# Sheet1.net
KiCad netlist of a schematic drawn in Altium Designer
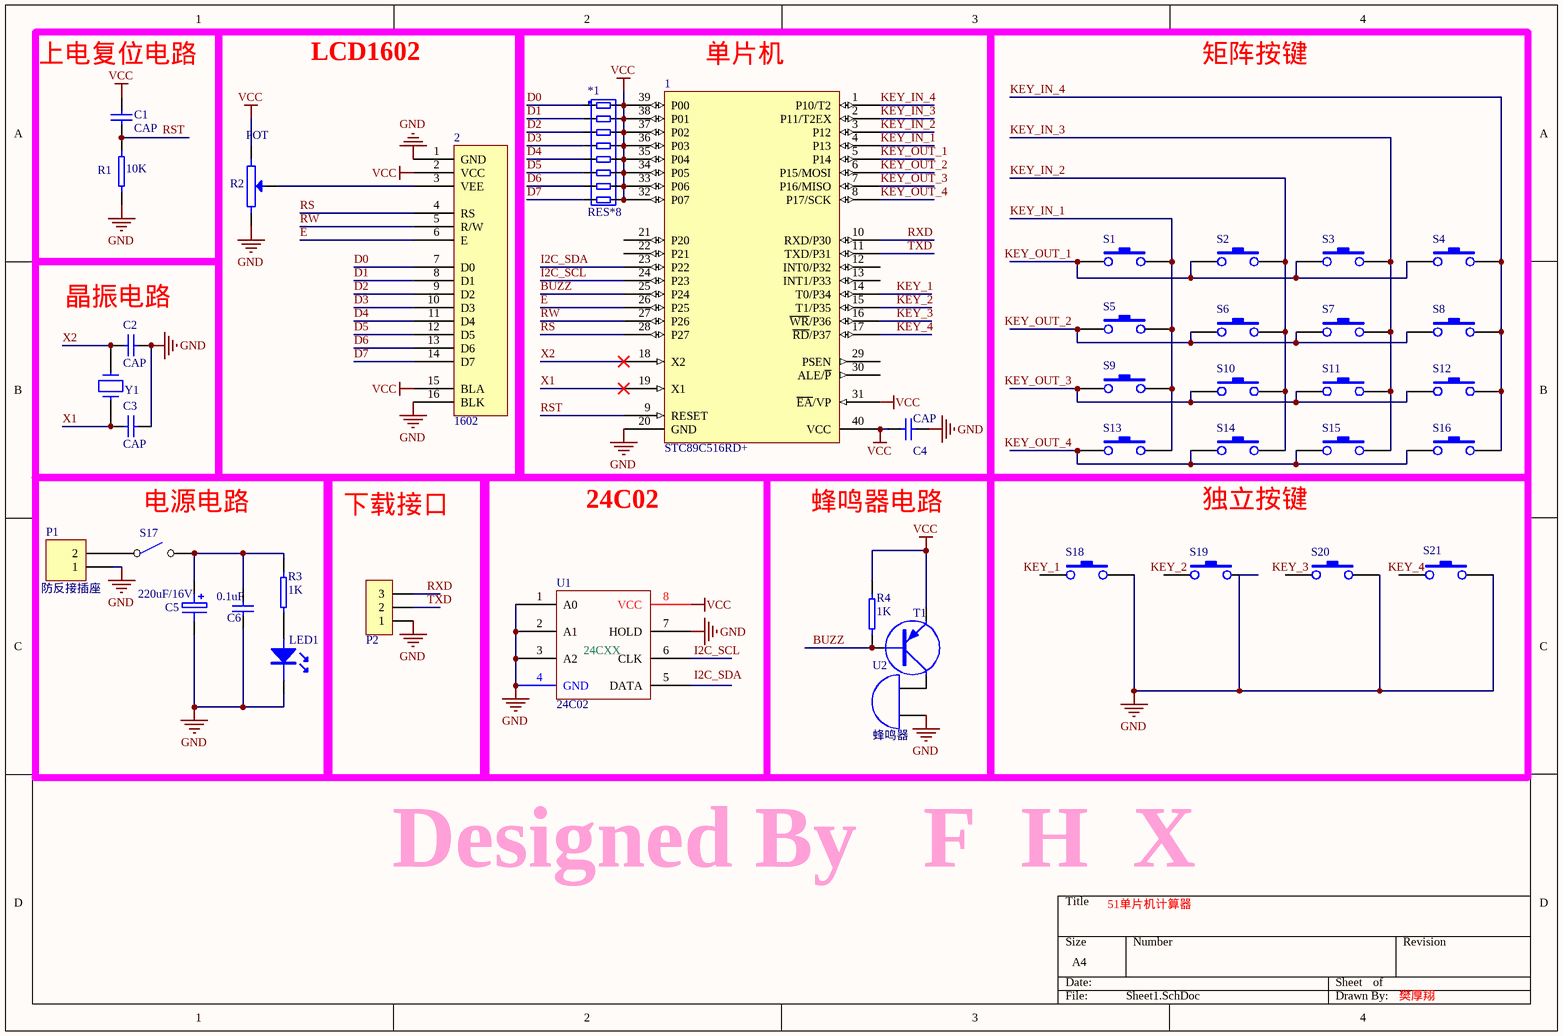
[diagram p0: Sheet1.SchDoc]

(export (version "E")
  (design (tool "Eeschema 10.0.6"))
  (components
    (comp (ref "*1") (value "RES*8") (footprint "SIP9") (libsource (lib "原理图封装库") (part "RES*8")))
    (comp (ref "1") (value "STC89C516RD+") (footprint "DIP-40") (libsource (lib "原理图封装库") (part "AT89S51")))
    (comp (ref "2") (value "1602") (footprint "SIP16") (libsource (lib "原理图封装库") (part "1602")))
    (comp (ref "C1") (value "CAP") (footprint "10UF") (libsource (lib "原理图封装库") (part "CAP")))
    (comp (ref "C2") (value "CAP") (footprint "10UF") (libsource (lib "原理图封装库") (part "CAP")))
    (comp (ref "C3") (value "CAP") (footprint "10UF") (libsource (lib "原理图封装库") (part "CAP")))
    (comp (ref "C4") (value "CAP") (footprint "10UF") (libsource (lib "原理图封装库") (part "CAP")))
    (comp (ref "C5")
      (value "220uF/16V")
      (footprint "RB.2/.4")
      (description "电解电容")
      (libsource (lib "Integrated_Library1") (part "CAP-E"))
    )
    (comp (ref "C6") (value "0.1uF") (footprint "10UF") (libsource (lib "原理图封装库") (part "CAP")))
    (comp (ref "LED1")
      (value "D-LED")
      (footprint "0805D")
      (description "LED")
      (libsource (lib "Integrated_Library1") (part "D-LED"))
    )
    (comp (ref "P1")
      (value "防反接插座")
      (footprint "HDR1X2")
      (description "Header, 2-Pin")
      (fields (field (name "PUBLISHER") "Altium Limited"))
      (libsource (lib "Miscellaneous Connectors") (part "Header 2"))
    )
    (comp (ref "P2") (value "CON3") (footprint "SIP3") (libsource (lib "原理图封装库") (part "CON3")))
    (comp (ref "R1") (value "10K") (footprint "AXIAL0.4") (libsource (lib "原理图封装库") (part "RES")))
    (comp (ref "R2") (value "POT") (footprint "RP3") (libsource (lib "原理图封装库") (part "POT")))
    (comp (ref "R3") (value "1K") (footprint "AXIAL0.4") (libsource (lib "原理图封装库") (part "RES")))
    (comp (ref "R4") (value "1K") (footprint "AXIAL0.4") (libsource (lib "原理图封装库") (part "RES")))
    (comp (ref "S1") (value "微动开关") (footprint "SWITCH") (libsource (lib "原理图封装库") (part "微动开关")))
    (comp (ref "S2") (value "微动开关") (footprint "SWITCH") (libsource (lib "原理图封装库") (part "微动开关")))
    (comp (ref "S3") (value "微动开关") (footprint "SWITCH") (libsource (lib "原理图封装库") (part "微动开关")))
    (comp (ref "S4") (value "微动开关") (footprint "SWITCH") (libsource (lib "原理图封装库") (part "微动开关")))
    (comp (ref "S5") (value "微动开关") (footprint "SWITCH") (libsource (lib "原理图封装库") (part "微动开关")))
    (comp (ref "S6") (value "微动开关") (footprint "SWITCH") (libsource (lib "原理图封装库") (part "微动开关")))
    (comp (ref "S7") (value "微动开关") (footprint "SWITCH") (libsource (lib "原理图封装库") (part "微动开关")))
    (comp (ref "S8") (value "微动开关") (footprint "SWITCH") (libsource (lib "原理图封装库") (part "微动开关")))
    (comp (ref "S9") (value "微动开关") (footprint "SWITCH") (libsource (lib "原理图封装库") (part "微动开关")))
    (comp (ref "S10") (value "微动开关") (footprint "SWITCH") (libsource (lib "原理图封装库") (part "微动开关")))
    (comp (ref "S11") (value "微动开关") (footprint "SWITCH") (libsource (lib "原理图封装库") (part "微动开关")))
    (comp (ref "S12") (value "微动开关") (footprint "SWITCH") (libsource (lib "原理图封装库") (part "微动开关")))
    (comp (ref "S13") (value "微动开关") (footprint "SWITCH") (libsource (lib "原理图封装库") (part "微动开关")))
    (comp (ref "S14") (value "微动开关") (footprint "SWITCH") (libsource (lib "原理图封装库") (part "微动开关")))
    (comp (ref "S15") (value "微动开关") (footprint "SWITCH") (libsource (lib "原理图封装库") (part "微动开关")))
    (comp (ref "S16") (value "微动开关") (footprint "SWITCH") (libsource (lib "原理图封装库") (part "微动开关")))
    (comp (ref "S17") (value "SW-SPST") (libsource (lib "Integrated_Library1") (part "SW-SPST")))
    (comp (ref "S18") (value "微动开关") (footprint "SWITCH") (libsource (lib "原理图封装库") (part "微动开关")))
    (comp (ref "S19") (value "微动开关") (footprint "SWITCH") (libsource (lib "原理图封装库") (part "微动开关")))
    (comp (ref "S20") (value "微动开关") (footprint "SWITCH") (libsource (lib "原理图封装库") (part "微动开关")))
    (comp (ref "S21") (value "微动开关") (footprint "SWITCH") (libsource (lib "原理图封装库") (part "微动开关")))
    (comp (ref "T1") (value "PNP") (footprint "TO92C") (libsource (lib "原理图封装库") (part "PNP")))
    (comp (ref "U1")
      (value "24C02")
      (footprint "DIP8")
      (libsource (lib "Integrated_Library1") (part "24CXX"))
    )
    (comp (ref "U2")
      (value "蜂鸣器")
      (footprint "RB3/7MM")
      (description "Bell")
      (libsource (lib "原理图封装库") (part "蜂鸣器"))
    )
    (comp (ref "Y1") (value "CRY") (footprint "XTAL1") (libsource (lib "原理图封装库") (part "CRY")))
  )
  (nets
    (net (code "1") (name "/BUZZ") (class "Default")
      (node (ref "1") (pin "25") (pinfunction "P24_25") (pintype "bidirectional"))
      (node (ref "R4") (pin "2") (pinfunction "2_2") (pintype "passive"))
      (node (ref "T1") (pin "1") (pinfunction "B_1") (pintype "passive"))
    )
    (net (code "2") (name "/D0") (class "Default")
      (node (ref "*1") (pin "1") (pintype "passive"))
      (node (ref "2") (pin "7") (pinfunction "D0_7") (pintype "passive"))
    )
    (net (code "3") (name "/D1") (class "Default")
      (node (ref "*1") (pin "2") (pintype "passive"))
      (node (ref "2") (pin "8") (pinfunction "D1_8") (pintype "passive"))
    )
    (net (code "4") (name "/D2") (class "Default")
      (node (ref "*1") (pin "3") (pintype "passive"))
      (node (ref "2") (pin "9") (pinfunction "D2_9") (pintype "passive"))
    )
    (net (code "5") (name "/D3") (class "Default")
      (node (ref "*1") (pin "4") (pintype "passive"))
      (node (ref "2") (pin "10") (pinfunction "D3_10") (pintype "passive"))
    )
    (net (code "6") (name "/D4") (class "Default")
      (node (ref "*1") (pin "5") (pintype "passive"))
      (node (ref "2") (pin "11") (pinfunction "D4_11") (pintype "passive"))
    )
    (net (code "7") (name "/D5") (class "Default")
      (node (ref "*1") (pin "6") (pintype "passive"))
      (node (ref "2") (pin "12") (pinfunction "D5_12") (pintype "passive"))
    )
    (net (code "8") (name "/D6") (class "Default")
      (node (ref "*1") (pin "7") (pintype "passive"))
      (node (ref "2") (pin "13") (pinfunction "D6_13") (pintype "passive"))
    )
    (net (code "9") (name "/D7") (class "Default")
      (node (ref "*1") (pin "8") (pintype "passive"))
      (node (ref "2") (pin "14") (pinfunction "D7_14") (pintype "passive"))
    )
    (net (code "10") (name "/E") (class "Default")
      (node (ref "1") (pin "26") (pinfunction "P25_26") (pintype "bidirectional"))
      (node (ref "2") (pin "6") (pinfunction "E_6") (pintype "passive"))
    )
    (net (code "11") (name "/I2C_SCL") (class "Default")
      (node (ref "1") (pin "24") (pinfunction "P23_24") (pintype "bidirectional"))
      (node (ref "U1") (pin "6") (pinfunction "CLK_6") (pintype "passive"))
    )
    (net (code "12") (name "/I2C_SDA") (class "Default")
      (node (ref "1") (pin "23") (pinfunction "P22_23") (pintype "bidirectional"))
    )
    (net (code "13") (name "/KEY_1") (class "Default")
      (node (ref "1") (pin "14") (pinfunction "T0/P34_14") (pintype "bidirectional"))
    )
    (net (code "14") (name "/KEY_2") (class "Default")
      (node (ref "1") (pin "15") (pinfunction "T1/P35_15") (pintype "bidirectional"))
    )
    (net (code "15") (name "/KEY_3") (class "Default")
      (node (ref "1") (pin "16") (pinfunction "~{WR}/P36_16") (pintype "bidirectional"))
    )
    (net (code "16") (name "/KEY_4") (class "Default")
      (node (ref "1") (pin "17") (pinfunction "~{RD}/P37_17") (pintype "bidirectional"))
    )
    (net (code "17") (name "/KEY_IN_1") (class "Default")
      (node (ref "1") (pin "4") (pinfunction "P13_4") (pintype "bidirectional"))
      (node (ref "S1") (pin "2") (pinfunction "2_2") (pintype "passive"))
      (node (ref "S13") (pin "2") (pinfunction "2_2") (pintype "passive"))
      (node (ref "S5") (pin "2") (pinfunction "2_2") (pintype "passive"))
      (node (ref "S9") (pin "2") (pinfunction "2_2") (pintype "passive"))
    )
    (net (code "18") (name "/KEY_IN_2") (class "Default")
      (node (ref "1") (pin "3") (pinfunction "P12_3") (pintype "bidirectional"))
      (node (ref "S10") (pin "2") (pinfunction "2_2") (pintype "passive"))
      (node (ref "S14") (pin "2") (pinfunction "2_2") (pintype "passive"))
      (node (ref "S2") (pin "2") (pinfunction "2_2") (pintype "passive"))
      (node (ref "S6") (pin "2") (pinfunction "2_2") (pintype "passive"))
    )
    (net (code "19") (name "/KEY_IN_3") (class "Default")
      (node (ref "1") (pin "2") (pinfunction "P11/T2EX_2") (pintype "bidirectional"))
      (node (ref "S11") (pin "2") (pinfunction "2_2") (pintype "passive"))
      (node (ref "S15") (pin "2") (pinfunction "2_2") (pintype "passive"))
      (node (ref "S3") (pin "2") (pinfunction "2_2") (pintype "passive"))
      (node (ref "S7") (pin "2") (pinfunction "2_2") (pintype "passive"))
    )
    (net (code "20") (name "/KEY_IN_4") (class "Default")
      (node (ref "1") (pin "1") (pinfunction "P10/T2_1") (pintype "bidirectional"))
      (node (ref "S12") (pin "2") (pinfunction "2_2") (pintype "passive"))
      (node (ref "S16") (pin "2") (pinfunction "2_2") (pintype "passive"))
      (node (ref "S4") (pin "2") (pinfunction "2_2") (pintype "passive"))
      (node (ref "S8") (pin "2") (pinfunction "2_2") (pintype "passive"))
    )
    (net (code "21") (name "/KEY_OUT_1") (class "Default")
      (node (ref "1") (pin "5") (pinfunction "P14_5") (pintype "bidirectional"))
    )
    (net (code "22") (name "/KEY_OUT_2") (class "Default")
      (node (ref "1") (pin "6") (pinfunction "P15/MOSI_6") (pintype "bidirectional"))
    )
    (net (code "23") (name "/KEY_OUT_3") (class "Default")
      (node (ref "1") (pin "7") (pinfunction "P16/MISO_7") (pintype "bidirectional"))
    )
    (net (code "24") (name "/KEY_OUT_4") (class "Default")
      (node (ref "1") (pin "8") (pinfunction "P17/SCK_8") (pintype "bidirectional"))
    )
    (net (code "25") (name "/RS") (class "Default")
      (node (ref "1") (pin "28") (pinfunction "P27_28") (pintype "bidirectional"))
      (node (ref "2") (pin "4") (pinfunction "RS_4") (pintype "passive"))
    )
    (net (code "26") (name "/RST") (class "Default")
      (node (ref "1") (pin "9") (pinfunction "RESET_9") (pintype "input"))
      (node (ref "C1") (pin "1") (pinfunction "1_1") (pintype "passive"))
      (node (ref "R1") (pin "2") (pinfunction "2_2") (pintype "passive"))
    )
    (net (code "27") (name "/RW") (class "Default")
      (node (ref "1") (pin "27") (pinfunction "P26_27") (pintype "bidirectional"))
      (node (ref "2") (pin "5") (pinfunction "R/W_5") (pintype "passive"))
    )
    (net (code "28") (name "/RXD") (class "Default")
      (node (ref "1") (pin "10") (pinfunction "RXD/P30_10") (pintype "bidirectional"))
      (node (ref "P2") (pin "3") (pinfunction "3_3") (pintype "passive"))
    )
    (net (code "29") (name "/TXD") (class "Default")
      (node (ref "1") (pin "11") (pinfunction "TXD/P31_11") (pintype "bidirectional"))
      (node (ref "P2") (pin "2") (pinfunction "2_2") (pintype "passive"))
    )
    (net (code "30") (name "/X1") (class "Default")
      (node (ref "1") (pin "19") (pinfunction "X1_19") (pintype "input"))
      (node (ref "C3") (pin "1") (pinfunction "1_1") (pintype "passive"))
      (node (ref "Y1") (pin "2") (pinfunction "2_2") (pintype "passive"))
    )
    (net (code "31") (name "/X2") (class "Default")
      (node (ref "1") (pin "18") (pinfunction "X2_18") (pintype "input"))
      (node (ref "C2") (pin "1") (pinfunction "1_1") (pintype "passive"))
      (node (ref "Y1") (pin "1") (pinfunction "1_1") (pintype "passive"))
    )
    (net (code "32") (name "GND") (class "Default")
      (node (ref "1") (pin "20") (pinfunction "GND_20") (pintype "passive"))
      (node (ref "2") (pin "1") (pinfunction "GND_1") (pintype "passive"))
      (node (ref "2") (pin "16") (pinfunction "BLK_16") (pintype "passive"))
      (node (ref "C2") (pin "2") (pinfunction "2_2") (pintype "passive"))
      (node (ref "C3") (pin "2") (pinfunction "2_2") (pintype "passive"))
      (node (ref "C4") (pin "1") (pinfunction "1_1") (pintype "passive"))
      (node (ref "C5") (pin "2") (pinfunction "2_2") (pintype "passive"))
      (node (ref "C6") (pin "1") (pinfunction "1_1") (pintype "passive"))
      (node (ref "LED1") (pin "K") (pinfunction "2_K") (pintype "passive"))
      (node (ref "P1") (pin "1") (pinfunction "1_1") (pintype "passive"))
      (node (ref "P2") (pin "1") (pinfunction "1_1") (pintype "passive"))
      (node (ref "R1") (pin "1") (pinfunction "1_1") (pintype "passive"))
      (node (ref "R2") (pin "3") (pinfunction "3_3") (pintype "passive"))
      (node (ref "S18") (pin "2") (pinfunction "2_2") (pintype "passive"))
      (node (ref "S19") (pin "2") (pinfunction "2_2") (pintype "passive"))
      (node (ref "S20") (pin "2") (pinfunction "2_2") (pintype "passive"))
      (node (ref "S21") (pin "2") (pinfunction "2_2") (pintype "passive"))
      (node (ref "U1") (pin "1") (pinfunction "A0_1") (pintype "passive"))
      (node (ref "U1") (pin "2") (pinfunction "A1_2") (pintype "passive"))
      (node (ref "U1") (pin "3") (pinfunction "A2_3") (pintype "passive"))
      (node (ref "U1") (pin "4") (pinfunction "GND_4") (pintype "passive"))
      (node (ref "U1") (pin "7") (pinfunction "HOLD_7") (pintype "passive"))
      (node (ref "U2") (pin "1") (pinfunction "A_1") (pintype "passive"))
    )
    (net (code "33") (name "Net-(2-VEE)") (class "Default")
      (node (ref "2") (pin "3") (pinfunction "VEE_3") (pintype "passive"))
      (node (ref "R2") (pin "2") (pinfunction "2_2") (pintype "passive"))
    )
    (net (code "34") (name "Net-(C5-Pad1)") (class "Default")
      (node (ref "C5") (pin "1") (pinfunction "1_1") (pintype "passive"))
      (node (ref "C6") (pin "2") (pinfunction "2_2") (pintype "passive"))
      (node (ref "R3") (pin "1") (pinfunction "1_1") (pintype "passive"))
      (node (ref "S17") (pin "2") (pinfunction "2_2") (pintype "passive"))
    )
    (net (code "35") (name "Net-(LED1-1)") (class "Default")
      (node (ref "LED1") (pin "A") (pinfunction "1_A") (pintype "passive"))
      (node (ref "R3") (pin "2") (pinfunction "2_2") (pintype "passive"))
    )
    (net (code "36") (name "Net-(P1-Pad2)") (class "Default")
      (node (ref "P1") (pin "2") (pinfunction "2_2") (pintype "passive"))
      (node (ref "S17") (pin "1") (pinfunction "1_1") (pintype "passive"))
    )
    (net (code "37") (name "Net-(S1-Pad1)") (class "Default")
      (node (ref "S1") (pin "1") (pinfunction "1_1") (pintype "passive"))
      (node (ref "S2") (pin "1") (pinfunction "1_1") (pintype "passive"))
      (node (ref "S3") (pin "1") (pinfunction "1_1") (pintype "passive"))
      (node (ref "S4") (pin "1") (pinfunction "1_1") (pintype "passive"))
    )
    (net (code "38") (name "Net-(S5-Pad1)") (class "Default")
      (node (ref "S5") (pin "1") (pinfunction "1_1") (pintype "passive"))
      (node (ref "S6") (pin "1") (pinfunction "1_1") (pintype "passive"))
      (node (ref "S7") (pin "1") (pinfunction "1_1") (pintype "passive"))
      (node (ref "S8") (pin "1") (pinfunction "1_1") (pintype "passive"))
    )
    (net (code "39") (name "Net-(S10-Pad1)") (class "Default")
      (node (ref "S10") (pin "1") (pinfunction "1_1") (pintype "passive"))
      (node (ref "S11") (pin "1") (pinfunction "1_1") (pintype "passive"))
      (node (ref "S12") (pin "1") (pinfunction "1_1") (pintype "passive"))
      (node (ref "S9") (pin "1") (pinfunction "1_1") (pintype "passive"))
    )
    (net (code "40") (name "Net-(S13-Pad1)") (class "Default")
      (node (ref "S13") (pin "1") (pinfunction "1_1") (pintype "passive"))
      (node (ref "S14") (pin "1") (pinfunction "1_1") (pintype "passive"))
      (node (ref "S15") (pin "1") (pinfunction "1_1") (pintype "passive"))
      (node (ref "S16") (pin "1") (pinfunction "1_1") (pintype "passive"))
    )
    (net (code "41") (name "Net-(T1-C)") (class "Default")
      (node (ref "T1") (pin "2") (pinfunction "C_2") (pintype "passive"))
      (node (ref "U2") (pin "2") (pinfunction "B_2") (pintype "passive"))
    )
    (net (code "42") (name "VCC") (class "Default")
      (node (ref "*1") (pin "10") (pintype "passive"))
      (node (ref "*1") (pin "11") (pintype "passive"))
      (node (ref "*1") (pin "12") (pintype "passive"))
      (node (ref "*1") (pin "13") (pintype "passive"))
      (node (ref "*1") (pin "14") (pintype "passive"))
      (node (ref "*1") (pin "15") (pintype "passive"))
      (node (ref "*1") (pin "16") (pintype "passive"))
      (node (ref "*1") (pin "9") (pintype "passive"))
      (node (ref "1") (pin "31") (pinfunction "~{EA}/VP_31") (pintype "input"))
      (node (ref "1") (pin "32") (pinfunction "P07_32") (pintype "bidirectional"))
      (node (ref "1") (pin "33") (pinfunction "P06_33") (pintype "bidirectional"))
      (node (ref "1") (pin "34") (pinfunction "P05_34") (pintype "bidirectional"))
      (node (ref "1") (pin "35") (pinfunction "P04_35") (pintype "bidirectional"))
      (node (ref "1") (pin "36") (pinfunction "P03_36") (pintype "bidirectional"))
      (node (ref "1") (pin "37") (pinfunction "P02_37") (pintype "bidirectional"))
      (node (ref "1") (pin "38") (pinfunction "P01_38") (pintype "bidirectional"))
      (node (ref "1") (pin "39") (pinfunction "P00_39") (pintype "bidirectional"))
      (node (ref "1") (pin "40") (pinfunction "VCC_40") (pintype "passive"))
      (node (ref "2") (pin "15") (pinfunction "BLA_15") (pintype "passive"))
      (node (ref "2") (pin "2") (pinfunction "VCC_2") (pintype "passive"))
      (node (ref "C1") (pin "2") (pinfunction "2_2") (pintype "passive"))
      (node (ref "C4") (pin "2") (pinfunction "2_2") (pintype "passive"))
      (node (ref "R2") (pin "1") (pinfunction "1_1") (pintype "passive"))
      (node (ref "R4") (pin "1") (pinfunction "1_1") (pintype "passive"))
      (node (ref "T1") (pin "3") (pinfunction "E_3") (pintype "passive"))
      (node (ref "U1") (pin "8") (pinfunction "VCC_8") (pintype "passive"))
    )
    (net (code "43") (name "unconnected-(1-ALE{slash}~{P}-Pad30)") (class "Default")
      (node (ref "1") (pin "30") (pinfunction "ALE/~{P}_30") (pintype "output"))
    )
    (net (code "44") (name "unconnected-(1-INT0{slash}P32-Pad12)") (class "Default")
      (node (ref "1") (pin "12") (pinfunction "INT0/P32_12") (pintype "bidirectional"))
    )
    (net (code "45") (name "unconnected-(1-INT1{slash}P33-Pad13)") (class "Default")
      (node (ref "1") (pin "13") (pinfunction "INT1/P33_13") (pintype "bidirectional"))
    )
    (net (code "46") (name "unconnected-(1-P20-Pad21)") (class "Default")
      (node (ref "1") (pin "21") (pinfunction "P20_21") (pintype "bidirectional"))
    )
    (net (code "47") (name "unconnected-(1-P21-Pad22)") (class "Default")
      (node (ref "1") (pin "22") (pinfunction "P21_22") (pintype "bidirectional"))
    )
    (net (code "48") (name "unconnected-(1-PSEN-Pad29)") (class "Default")
      (node (ref "1") (pin "29") (pinfunction "PSEN_29") (pintype "output"))
    )
    (net (code "49") (name "unconnected-(S18-Pad1)") (class "Default")
      (node (ref "S18") (pin "1") (pinfunction "1_1") (pintype "passive"))
    )
    (net (code "50") (name "unconnected-(S19-Pad1)") (class "Default")
      (node (ref "S19") (pin "1") (pinfunction "1_1") (pintype "passive"))
    )
    (net (code "51") (name "unconnected-(S20-Pad1)") (class "Default")
      (node (ref "S20") (pin "1") (pinfunction "1_1") (pintype "passive"))
    )
    (net (code "52") (name "unconnected-(S21-Pad1)") (class "Default")
      (node (ref "S21") (pin "1") (pinfunction "1_1") (pintype "passive"))
    )
    (net (code "53") (name "unconnected-(U1-DATA-Pad5)") (class "Default")
      (node (ref "U1") (pin "5") (pinfunction "DATA_5") (pintype "passive"))
    )
  )
)
